# Sheet1.net
KiCad netlist of a schematic drawn in Altium Designer
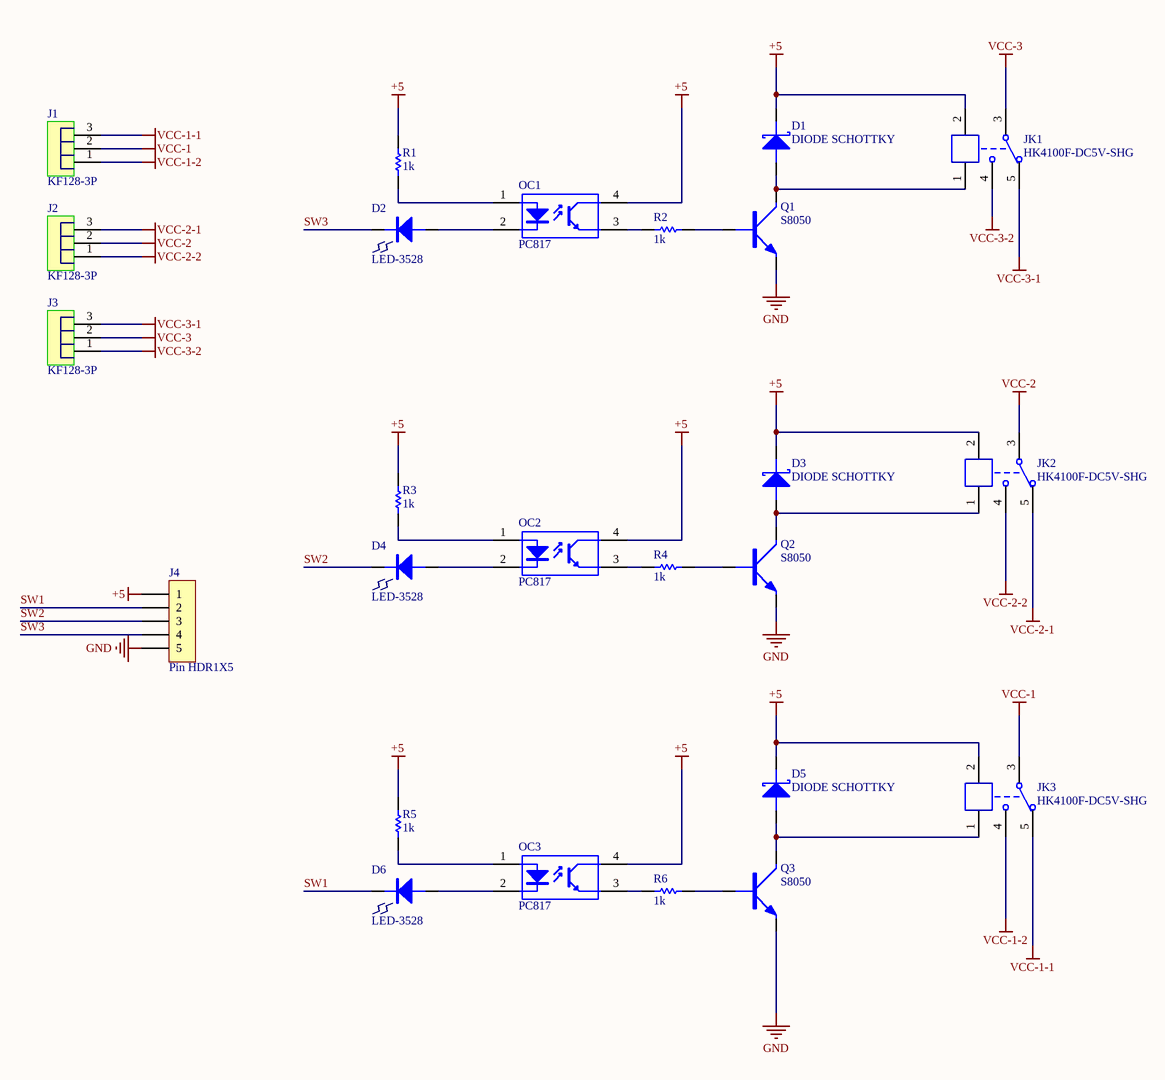
[diagram p0: Sheet1.SchDoc]

(export (version "E")
  (design (tool "Eeschema 10.0.6"))
  (components
    (comp (ref "D1")
      (value "DIODE SCHOTTKY")
      (footprint "SMA/DO-214AC")
      (description "肖特基二极管")
      (libsource (lib "常用元件-二极管") (part "DIODE SCHOTTKY"))
    )
    (comp (ref "D2")
      (value "LED-3528")
      (footprint "LED-3528R")
      (libsource (lib "常用元件-LED") (part "LED-3528"))
    )
    (comp (ref "D3")
      (value "DIODE SCHOTTKY")
      (footprint "SMA/DO-214AC")
      (description "肖特基二极管")
      (libsource (lib "常用元件-二极管") (part "DIODE SCHOTTKY"))
    )
    (comp (ref "D4")
      (value "LED-3528")
      (footprint "LED-3528R")
      (libsource (lib "常用元件-LED") (part "LED-3528"))
    )
    (comp (ref "D5")
      (value "DIODE SCHOTTKY")
      (footprint "SMA/DO-214AC")
      (description "肖特基二极管")
      (libsource (lib "常用元件-二极管") (part "DIODE SCHOTTKY"))
    )
    (comp (ref "D6")
      (value "LED-3528")
      (footprint "LED-3528R")
      (libsource (lib "常用元件-LED") (part "LED-3528"))
    )
    (comp (ref "J1")
      (value "KF128-3P")
      (footprint "KF128-3.81-3P")
      (libsource (lib "插接类-KF128") (part "KF128-3P"))
    )
    (comp (ref "J2")
      (value "KF128-3P")
      (footprint "KF128-3.81-3P")
      (libsource (lib "插接类-KF128") (part "KF128-3P"))
    )
    (comp (ref "J3")
      (value "KF128-3P")
      (footprint "KF128-3.81-3P")
      (libsource (lib "插接类-KF128") (part "KF128-3P"))
    )
    (comp (ref "J4")
      (value "Pin HDR1X5")
      (footprint "Pin HDR1X5/2.54mm-S")
      (libsource (lib "常用元件-排针") (part "Pin HDR1X5"))
    )
    (comp (ref "JK1")
      (value "HK4100F-DC5V-SHG")
      (footprint "HK4100F")
      (description "一组转换")
      (libsource (lib "开关-继电器") (part "HK4100F"))
    )
    (comp (ref "JK2")
      (value "HK4100F-DC5V-SHG")
      (footprint "HK4100F")
      (description "一组转换")
      (libsource (lib "开关-继电器") (part "HK4100F"))
    )
    (comp (ref "JK3")
      (value "HK4100F-DC5V-SHG")
      (footprint "HK4100F")
      (description "一组转换")
      (libsource (lib "开关-继电器") (part "HK4100F"))
    )
    (comp (ref "OC1")
      (value "PC817")
      (footprint "SMD_PC817")
      (description "线性光耦")
      (libsource (lib "光电隔离器") (part "PC817"))
    )
    (comp (ref "OC2")
      (value "PC817")
      (footprint "SMD_PC817")
      (description "线性光耦")
      (libsource (lib "光电隔离器") (part "PC817"))
    )
    (comp (ref "OC3")
      (value "PC817")
      (footprint "SMD_PC817")
      (description "线性光耦")
      (libsource (lib "光电隔离器") (part "PC817"))
    )
    (comp (ref "Q1")
      (value "S8050")
      (footprint "SOT-23")
      (description "NPN三极管")
      (libsource (lib "常用元件-三极管") (part "NPN"))
    )
    (comp (ref "Q2")
      (value "S8050")
      (footprint "SOT-23")
      (description "NPN三极管")
      (libsource (lib "常用元件-三极管") (part "NPN"))
    )
    (comp (ref "Q3")
      (value "S8050")
      (footprint "SOT-23")
      (description "NPN三极管")
      (libsource (lib "常用元件-三极管") (part "NPN"))
    )
    (comp (ref "R1") (value "1k") (footprint "0805R") (libsource (lib "常用元件-电阻") (part "RES")))
    (comp (ref "R2") (value "1k") (footprint "0805R") (libsource (lib "常用元件-电阻") (part "RES")))
    (comp (ref "R3") (value "1k") (footprint "0805R") (libsource (lib "常用元件-电阻") (part "RES")))
    (comp (ref "R4") (value "1k") (footprint "0805R") (libsource (lib "常用元件-电阻") (part "RES")))
    (comp (ref "R5") (value "1k") (footprint "0805R") (libsource (lib "常用元件-电阻") (part "RES")))
    (comp (ref "R6") (value "1k") (footprint "0805R") (libsource (lib "常用元件-电阻") (part "RES")))
  )
  (nets
    (net (code "1") (name "+5") (class "Default")
      (node (ref "D1") (pin "K") (pinfunction "K_K") (pintype "passive"))
      (node (ref "D3") (pin "K") (pinfunction "K_K") (pintype "passive"))
      (node (ref "D5") (pin "K") (pinfunction "K_K") (pintype "passive"))
      (node (ref "J4") (pin "1") (pinfunction "1_1") (pintype "passive"))
      (node (ref "JK1") (pin "2") (pinfunction "2_2") (pintype "passive"))
      (node (ref "JK2") (pin "2") (pinfunction "2_2") (pintype "passive"))
      (node (ref "JK3") (pin "2") (pinfunction "2_2") (pintype "passive"))
      (node (ref "OC1") (pin "4") (pinfunction "C_4") (pintype "passive"))
      (node (ref "OC2") (pin "4") (pinfunction "C_4") (pintype "passive"))
      (node (ref "OC3") (pin "4") (pinfunction "C_4") (pintype "passive"))
      (node (ref "R1") (pin "1") (pinfunction "1_1") (pintype "passive"))
      (node (ref "R3") (pin "1") (pinfunction "1_1") (pintype "passive"))
      (node (ref "R5") (pin "1") (pinfunction "1_1") (pintype "passive"))
    )
    (net (code "2") (name "/SW1") (class "Default")
      (node (ref "D6") (pin "K") (pinfunction "K_K") (pintype "passive"))
      (node (ref "J4") (pin "2") (pinfunction "2_2") (pintype "passive"))
    )
    (net (code "3") (name "/SW2") (class "Default")
      (node (ref "D4") (pin "K") (pinfunction "K_K") (pintype "passive"))
      (node (ref "J4") (pin "3") (pinfunction "3_3") (pintype "passive"))
    )
    (net (code "4") (name "/SW3") (class "Default")
      (node (ref "D2") (pin "K") (pinfunction "K_K") (pintype "passive"))
      (node (ref "J4") (pin "4") (pinfunction "4_4") (pintype "passive"))
    )
    (net (code "5") (name "GND") (class "Default")
      (node (ref "J4") (pin "5") (pinfunction "5_5") (pintype "passive"))
      (node (ref "Q1") (pin "E") (pinfunction "E_E") (pintype "passive"))
      (node (ref "Q2") (pin "E") (pinfunction "E_E") (pintype "passive"))
      (node (ref "Q3") (pin "E") (pinfunction "E_E") (pintype "passive"))
    )
    (net (code "6") (name "Net-(D1-PadA)") (class "Default")
      (node (ref "D1") (pin "A") (pinfunction "A_A") (pintype "passive"))
      (node (ref "JK1") (pin "1") (pinfunction "1_1") (pintype "passive"))
      (node (ref "Q1") (pin "C") (pinfunction "C_C") (pintype "passive"))
    )
    (net (code "7") (name "Net-(D3-PadA)") (class "Default")
      (node (ref "D3") (pin "A") (pinfunction "A_A") (pintype "passive"))
      (node (ref "JK2") (pin "1") (pinfunction "1_1") (pintype "passive"))
      (node (ref "Q2") (pin "C") (pinfunction "C_C") (pintype "passive"))
    )
    (net (code "8") (name "Net-(D5-PadA)") (class "Default")
      (node (ref "D5") (pin "A") (pinfunction "A_A") (pintype "passive"))
      (node (ref "JK3") (pin "1") (pinfunction "1_1") (pintype "passive"))
      (node (ref "Q3") (pin "C") (pinfunction "C_C") (pintype "passive"))
    )
    (net (code "9") (name "Net-(OC1-A)") (class "Default")
      (node (ref "OC1") (pin "1") (pinfunction "A_1") (pintype "passive"))
      (node (ref "R1") (pin "2") (pinfunction "2_2") (pintype "passive"))
    )
    (net (code "10") (name "Net-(OC1-E)") (class "Default")
      (node (ref "OC1") (pin "3") (pinfunction "E_3") (pintype "passive"))
      (node (ref "R2") (pin "2") (pinfunction "2_2") (pintype "passive"))
    )
    (net (code "11") (name "Net-(OC1-K)") (class "Default")
      (node (ref "D2") (pin "A") (pinfunction "A_A") (pintype "passive"))
      (node (ref "OC1") (pin "2") (pinfunction "K_2") (pintype "passive"))
    )
    (net (code "12") (name "Net-(OC2-A)") (class "Default")
      (node (ref "OC2") (pin "1") (pinfunction "A_1") (pintype "passive"))
      (node (ref "R3") (pin "2") (pinfunction "2_2") (pintype "passive"))
    )
    (net (code "13") (name "Net-(OC2-E)") (class "Default")
      (node (ref "OC2") (pin "3") (pinfunction "E_3") (pintype "passive"))
      (node (ref "R4") (pin "2") (pinfunction "2_2") (pintype "passive"))
    )
    (net (code "14") (name "Net-(OC2-K)") (class "Default")
      (node (ref "D4") (pin "A") (pinfunction "A_A") (pintype "passive"))
      (node (ref "OC2") (pin "2") (pinfunction "K_2") (pintype "passive"))
    )
    (net (code "15") (name "Net-(OC3-A)") (class "Default")
      (node (ref "OC3") (pin "1") (pinfunction "A_1") (pintype "passive"))
      (node (ref "R5") (pin "2") (pinfunction "2_2") (pintype "passive"))
    )
    (net (code "16") (name "Net-(OC3-E)") (class "Default")
      (node (ref "OC3") (pin "3") (pinfunction "E_3") (pintype "passive"))
      (node (ref "R6") (pin "2") (pinfunction "2_2") (pintype "passive"))
    )
    (net (code "17") (name "Net-(OC3-K)") (class "Default")
      (node (ref "D6") (pin "A") (pinfunction "A_A") (pintype "passive"))
      (node (ref "OC3") (pin "2") (pinfunction "K_2") (pintype "passive"))
    )
    (net (code "18") (name "Net-(Q1-PadB)") (class "Default")
      (node (ref "Q1") (pin "B") (pinfunction "B_B") (pintype "passive"))
      (node (ref "R2") (pin "1") (pinfunction "1_1") (pintype "passive"))
    )
    (net (code "19") (name "Net-(Q2-PadB)") (class "Default")
      (node (ref "Q2") (pin "B") (pinfunction "B_B") (pintype "passive"))
      (node (ref "R4") (pin "1") (pinfunction "1_1") (pintype "passive"))
    )
    (net (code "20") (name "Net-(Q3-PadB)") (class "Default")
      (node (ref "Q3") (pin "B") (pinfunction "B_B") (pintype "passive"))
      (node (ref "R6") (pin "1") (pinfunction "1_1") (pintype "passive"))
    )
    (net (code "21") (name "VCC-1") (class "Default")
      (node (ref "J1") (pin "2") (pinfunction "2_2") (pintype "passive"))
      (node (ref "JK3") (pin "3") (pinfunction "3_3") (pintype "passive"))
    )
    (net (code "22") (name "VCC-1-1") (class "Default")
      (node (ref "J1") (pin "3") (pinfunction "3_3") (pintype "passive"))
      (node (ref "JK3") (pin "5") (pinfunction "5_5") (pintype "passive"))
    )
    (net (code "23") (name "VCC-1-2") (class "Default")
      (node (ref "J1") (pin "1") (pinfunction "1_1") (pintype "passive"))
      (node (ref "JK3") (pin "4") (pinfunction "4_4") (pintype "passive"))
    )
    (net (code "24") (name "VCC-2") (class "Default")
      (node (ref "J2") (pin "2") (pinfunction "2_2") (pintype "passive"))
      (node (ref "JK2") (pin "3") (pinfunction "3_3") (pintype "passive"))
    )
    (net (code "25") (name "VCC-2-1") (class "Default")
      (node (ref "J2") (pin "3") (pinfunction "3_3") (pintype "passive"))
      (node (ref "JK2") (pin "5") (pinfunction "5_5") (pintype "passive"))
    )
    (net (code "26") (name "VCC-2-2") (class "Default")
      (node (ref "J2") (pin "1") (pinfunction "1_1") (pintype "passive"))
      (node (ref "JK2") (pin "4") (pinfunction "4_4") (pintype "passive"))
    )
    (net (code "27") (name "VCC-3") (class "Default")
      (node (ref "J3") (pin "2") (pinfunction "2_2") (pintype "passive"))
      (node (ref "JK1") (pin "3") (pinfunction "3_3") (pintype "passive"))
    )
    (net (code "28") (name "VCC-3-1") (class "Default")
      (node (ref "J3") (pin "3") (pinfunction "3_3") (pintype "passive"))
      (node (ref "JK1") (pin "5") (pinfunction "5_5") (pintype "passive"))
    )
    (net (code "29") (name "VCC-3-2") (class "Default")
      (node (ref "J3") (pin "1") (pinfunction "1_1") (pintype "passive"))
      (node (ref "JK1") (pin "4") (pinfunction "4_4") (pintype "passive"))
    )
  )
)
